# Sensors_A_Data.net
KiCad netlist of a schematic drawn in Altium Designer
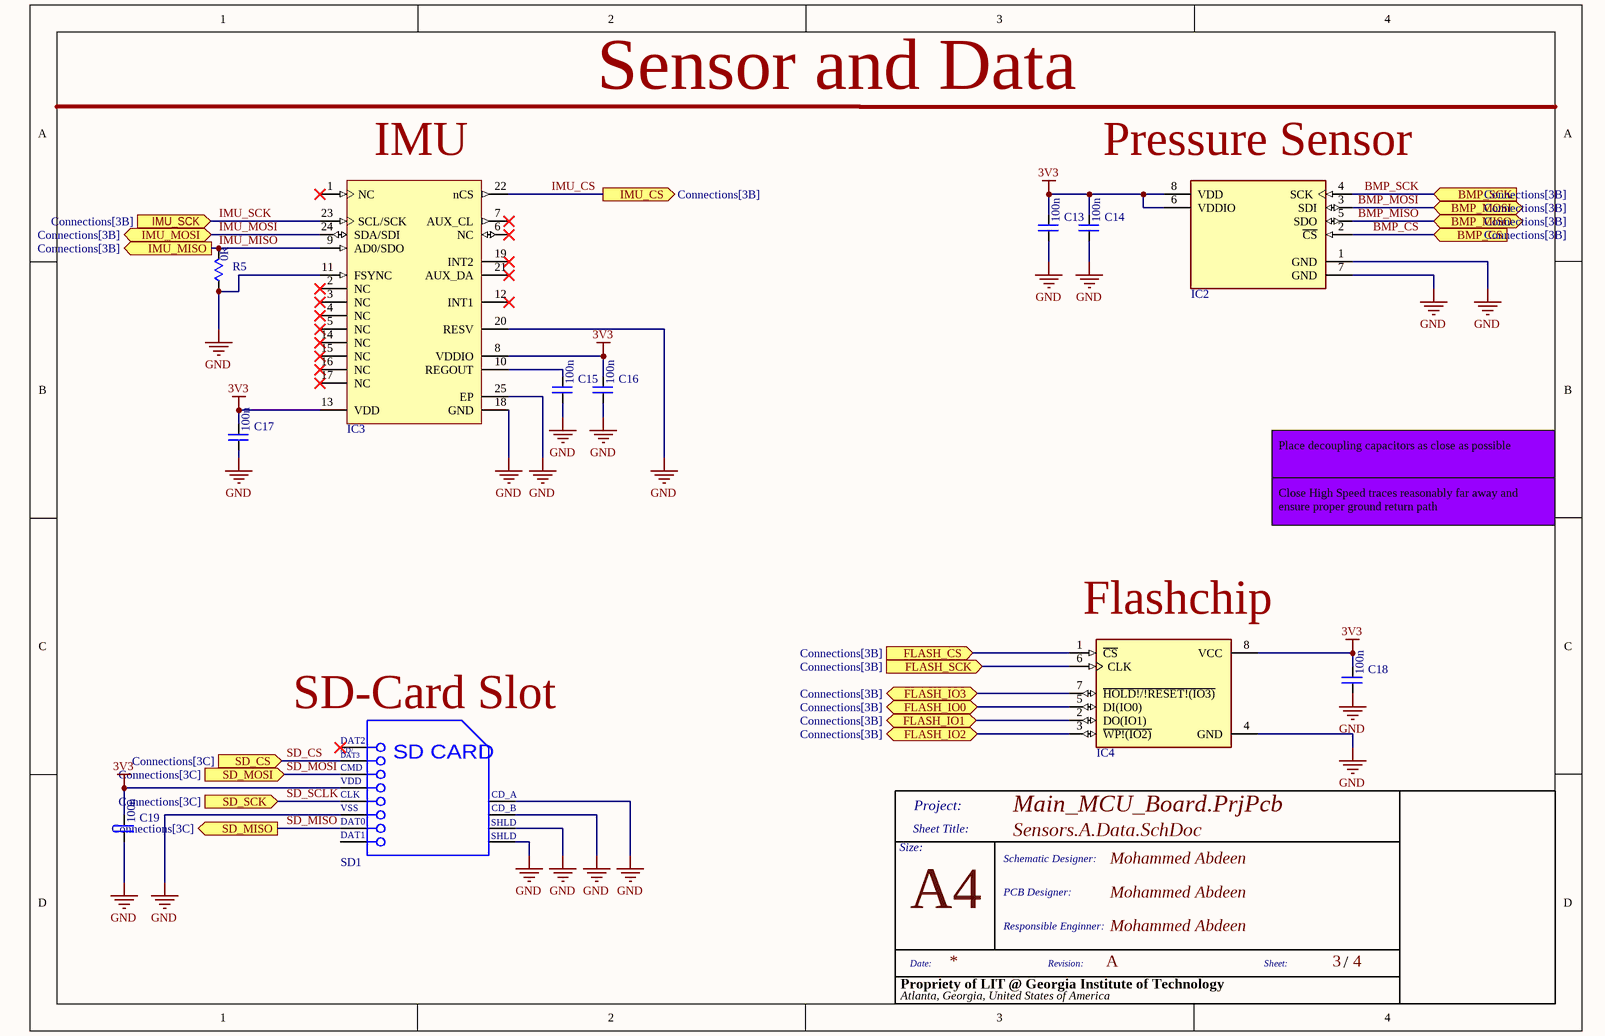
[diagram p0: Sensors.A.Data.SchDoc]

(export (version "E")
  (design (tool "Eeschema 10.0.6"))
  (components
    (comp (ref "C13")
      (value "KGM21NR71E104KT")
      (footprint "CAP-0805")
      (description "0.1 µF ±10% 25V Ceramic Capacitor X7R 0805 (2012 Metric)")
      (libsource (lib "MainMCUSch") (part "CAP-0805-25V-100n"))
    )
    (comp (ref "C14")
      (value "KGM21NR71E104KT")
      (footprint "CAP-0805")
      (description "0.1 µF ±10% 25V Ceramic Capacitor X7R 0805 (2012 Metric)")
      (libsource (lib "MainMCUSch") (part "CAP-0805-25V-100n"))
    )
    (comp (ref "C15")
      (value "KGM21NR71E104KT")
      (footprint "CAP-0805")
      (description "0.1 µF ±10% 25V Ceramic Capacitor X7R 0805 (2012 Metric)")
      (libsource (lib "MainMCUSch") (part "CAP-0805-25V-100n"))
    )
    (comp (ref "C16")
      (value "KGM21NR71E104KT")
      (footprint "CAP-0805")
      (description "0.1 µF ±10% 25V Ceramic Capacitor X7R 0805 (2012 Metric)")
      (libsource (lib "MainMCUSch") (part "CAP-0805-25V-100n"))
    )
    (comp (ref "C17")
      (value "KGM21NR71E104KT")
      (footprint "CAP-0805")
      (description "0.1 µF ±10% 25V Ceramic Capacitor X7R 0805 (2012 Metric)")
      (libsource (lib "MainMCUSch") (part "CAP-0805-25V-100n"))
    )
    (comp (ref "C18")
      (value "KGM21NR71E104KT")
      (footprint "CAP-0805")
      (description "0.1 µF ±10% 25V Ceramic Capacitor X7R 0805 (2012 Metric)")
      (libsource (lib "MainMCUSch") (part "CAP-0805-25V-100n"))
    )
    (comp (ref "C19")
      (value "KGM21NR71E104KT")
      (footprint "CAP-0805")
      (description "0.1 µF ±10% 25V Ceramic Capacitor X7R 0805 (2012 Metric)")
      (libsource (lib "MainMCUSch") (part "CAP-0805-25V-100n"))
    )
    (comp (ref "IC2")
      (value "BME280")
      (footprint "BME280")
      (description "Pressure Sensor 4.35PSI ~ 15.95PSI (30kPa ~ 110kPa) Absolute 16b 8-SMD")
      (libsource (lib "MainMCUSch") (part "BME280"))
    )
    (comp (ref "IC3")
      (value "ICM-20649")
      (footprint "24-QFN")
      (description "Accelerometer, Gyroscope, Temperature, 6 Axis Sensor I2C, SPI Output")
      (libsource (lib "MainMCUSch") (part "IMU-ICM20649-SPI"))
    )
    (comp (ref "IC4")
      (value "W25Q32JVSSIQ")
      (footprint "F-SOIC127P790X216-8N")
      (description "FLASH - NOR Memory IC 32Mbit SPI - Quad I/O 133 MHz 8-SOIC")
      (libsource (lib "MainMCUSch") (part "Flashchip-32MBIT-3V3"))
    )
    (comp (ref "R5")
      (value "ERJ-6GEY0R00V")
      (footprint "0805-RES")
      (description "0 Ohms Jumper Chip Resistor 0805 (2012 Metric) Automotive AEC-Q200 Thick Film")
      (libsource (lib "MainMCUSch") (part "RES-0805-0R"))
    )
    (comp (ref "SD1")
      (value "1040310811")
      (footprint "MOLX-104031-0811_V")
      (description "10 (8 + 2) Position Card Connector Secure Digital - microSD™ Surface Mount, Right Angle Gold")
      (fields (field (name "MANUFACTURER") "Molex"))
      (libsource (lib "MainMCUSch") (part "microSD-card-connector"))
    )
  )
  (nets
    (net (code "1") (name "/BMP_CS") (class "Default")
      (node (ref "IC2") (pin "2") (pinfunction "~{CS}_2") (pintype "input"))
    )
    (net (code "2") (name "/BMP_MISO") (class "Default")
      (node (ref "IC2") (pin "5") (pinfunction "SDO_5") (pintype "bidirectional"))
    )
    (net (code "3") (name "/BMP_MOSI") (class "Default")
      (node (ref "IC2") (pin "3") (pinfunction "SDI_3") (pintype "bidirectional"))
    )
    (net (code "4") (name "/BMP_SCK") (class "Default")
      (node (ref "IC2") (pin "4") (pinfunction "SCK_4") (pintype "input"))
    )
    (net (code "5") (name "/FLASH_CS") (class "Default")
      (node (ref "IC4") (pin "1") (pinfunction "~{CS}_1") (pintype "input"))
    )
    (net (code "6") (name "/FLASH_IO0") (class "Default")
      (node (ref "IC4") (pin "5") (pinfunction "DI(IO0)_5") (pintype "bidirectional"))
    )
    (net (code "7") (name "/FLASH_IO1") (class "Default")
      (node (ref "IC4") (pin "2") (pinfunction "DO(IO1)_2") (pintype "bidirectional"))
    )
    (net (code "8") (name "/FLASH_IO2") (class "Default")
      (node (ref "IC4") (pin "3") (pinfunction "~{WP!(IO2)}_3") (pintype "bidirectional"))
    )
    (net (code "9") (name "/FLASH_IO3") (class "Default")
      (node (ref "IC4") (pin "7") (pinfunction "~{HOLD!/!RESET!(IO3)}_7") (pintype "bidirectional"))
    )
    (net (code "10") (name "/FLASH_SCK") (class "Default")
      (node (ref "IC4") (pin "6") (pinfunction "CLK_6") (pintype "input"))
    )
    (net (code "11") (name "/IMU_CS") (class "Default")
      (node (ref "IC3") (pin "22") (pinfunction "nCS_22") (pintype "output"))
    )
    (net (code "12") (name "/IMU_MISO") (class "Default")
      (node (ref "IC3") (pin "9") (pinfunction "AD0/SDO_9") (pintype "input"))
      (node (ref "R5") (pin "2") (pintype "passive"))
    )
    (net (code "13") (name "/IMU_MOSI") (class "Default")
      (node (ref "IC3") (pin "24") (pinfunction "SDA/SDI_24") (pintype "bidirectional"))
    )
    (net (code "14") (name "/IMU_SCK") (class "Default")
      (node (ref "IC3") (pin "23") (pinfunction "SCL/SCK_23") (pintype "input"))
    )
    (net (code "15") (name "/SD_CS") (class "Default")
      (node (ref "SD1") (pin "2") (pinfunction "CMD_2") (pintype "passive"))
    )
    (net (code "16") (name "/SD_MISO") (class "Default")
      (node (ref "SD1") (pin "7") (pinfunction "DAT0_7") (pintype "passive"))
    )
    (net (code "17") (name "/SD_MOSI") (class "Default")
      (node (ref "SD1") (pin "3") (pinfunction "VSS1_3") (pintype "passive"))
    )
    (net (code "18") (name "/SD_SCLK") (class "Default")
      (node (ref "SD1") (pin "5") (pinfunction "CLK_5") (pintype "passive"))
    )
    (net (code "19") (name "3V3") (class "Default")
      (node (ref "C13") (pin "2") (pintype "passive"))
      (node (ref "C14") (pin "2") (pintype "passive"))
      (node (ref "C16") (pin "2") (pintype "passive"))
      (node (ref "C17") (pin "2") (pintype "passive"))
      (node (ref "C18") (pin "2") (pintype "passive"))
      (node (ref "C19") (pin "2") (pintype "passive"))
      (node (ref "IC2") (pin "6") (pinfunction "VDDIO_6") (pintype "power_in"))
      (node (ref "IC2") (pin "8") (pinfunction "VDD_8") (pintype "power_in"))
      (node (ref "IC3") (pin "13") (pinfunction "VDD_13") (pintype "power_in"))
      (node (ref "IC3") (pin "8") (pinfunction "VDDIO_8") (pintype "power_in"))
      (node (ref "IC4") (pin "8") (pinfunction "VCC_8") (pintype "power_in"))
      (node (ref "SD1") (pin "4") (pinfunction "VDD_4") (pintype "passive"))
    )
    (net (code "20") (name "GND") (class "Default")
      (node (ref "C13") (pin "1") (pintype "passive"))
      (node (ref "C14") (pin "1") (pintype "passive"))
      (node (ref "C15") (pin "1") (pintype "passive"))
      (node (ref "C16") (pin "1") (pintype "passive"))
      (node (ref "C17") (pin "1") (pintype "passive"))
      (node (ref "C18") (pin "1") (pintype "passive"))
      (node (ref "C19") (pin "1") (pintype "passive"))
      (node (ref "IC2") (pin "1") (pinfunction "GND_1") (pintype "power_in"))
      (node (ref "IC2") (pin "7") (pinfunction "GND_7") (pintype "power_in"))
      (node (ref "IC3") (pin "11") (pinfunction "FSYNC_11") (pintype "input"))
      (node (ref "IC3") (pin "18") (pinfunction "GND_18") (pintype "power_in"))
      (node (ref "IC3") (pin "20") (pinfunction "RESV_20") (pintype "passive"))
      (node (ref "IC3") (pin "25") (pinfunction "EP_25") (pintype "power_in"))
      (node (ref "IC4") (pin "4") (pinfunction "GND_4") (pintype "power_in"))
      (node (ref "R5") (pin "1") (pintype "passive"))
      (node (ref "SD1") (pin "10") (pinfunction "CD_B_10") (pintype "passive"))
      (node (ref "SD1") (pin "11") (pinfunction "SHLD1_11") (pintype "passive"))
      (node (ref "SD1") (pin "12") (pinfunction "SHLD2_12") (pintype "passive"))
      (node (ref "SD1") (pin "6") (pinfunction "VSS2_6") (pintype "passive"))
      (node (ref "SD1") (pin "9") (pinfunction "CD_A_9") (pintype "passive"))
    )
    (net (code "21") (name "Net-(IC3-REGOUT)") (class "Default")
      (node (ref "C15") (pin "2") (pintype "passive"))
      (node (ref "IC3") (pin "10") (pinfunction "REGOUT_10") (pintype "passive"))
    )
    (net (code "22") (name "unconnected-(IC3-AUX_CL-Pad7)") (class "Default")
      (node (ref "IC3") (pin "7") (pinfunction "AUX_CL_7") (pintype "output+no_connect"))
    )
    (net (code "23") (name "unconnected-(IC3-AUX_DA-Pad21)") (class "Default")
      (node (ref "IC3") (pin "21") (pinfunction "AUX_DA_21") (pintype "passive+no_connect"))
    )
    (net (code "24") (name "unconnected-(IC3-INT1-Pad12)") (class "Default")
      (node (ref "IC3") (pin "12") (pinfunction "INT1_12") (pintype "open_collector+no_connect"))
    )
    (net (code "25") (name "unconnected-(IC3-INT2-Pad19)") (class "Default")
      (node (ref "IC3") (pin "19") (pinfunction "INT2_19") (pintype "passive+no_connect"))
    )
    (net (code "26") (name "unconnected-(IC3-NC-Pad1)") (class "Default")
      (node (ref "IC3") (pin "1") (pinfunction "NC_1") (pintype "input+no_connect"))
    )
    (net (code "27") (name "unconnected-(IC3-NC-Pad2)") (class "Default")
      (node (ref "IC3") (pin "2") (pinfunction "NC_2") (pintype "passive+no_connect"))
    )
    (net (code "28") (name "unconnected-(IC3-NC-Pad3)") (class "Default")
      (node (ref "IC3") (pin "3") (pinfunction "NC_3") (pintype "passive+no_connect"))
    )
    (net (code "29") (name "unconnected-(IC3-NC-Pad4)") (class "Default")
      (node (ref "IC3") (pin "4") (pinfunction "NC_4") (pintype "passive+no_connect"))
    )
    (net (code "30") (name "unconnected-(IC3-NC-Pad5)") (class "Default")
      (node (ref "IC3") (pin "5") (pinfunction "NC_5") (pintype "passive+no_connect"))
    )
    (net (code "31") (name "unconnected-(IC3-NC-Pad6)") (class "Default")
      (node (ref "IC3") (pin "6") (pinfunction "NC_6") (pintype "bidirectional+no_connect"))
    )
    (net (code "32") (name "unconnected-(IC3-NC-Pad14)") (class "Default")
      (node (ref "IC3") (pin "14") (pinfunction "NC_14") (pintype "passive+no_connect"))
    )
    (net (code "33") (name "unconnected-(IC3-NC-Pad15)") (class "Default")
      (node (ref "IC3") (pin "15") (pinfunction "NC_15") (pintype "passive+no_connect"))
    )
    (net (code "34") (name "unconnected-(IC3-NC-Pad16)") (class "Default")
      (node (ref "IC3") (pin "16") (pinfunction "NC_16") (pintype "passive+no_connect"))
    )
    (net (code "35") (name "unconnected-(IC3-NC-Pad17)") (class "Default")
      (node (ref "IC3") (pin "17") (pinfunction "NC_17") (pintype "passive+no_connect"))
    )
    (net (code "36") (name "unconnected-(SD1-CD{slash}DAT3-Pad1)") (class "Default")
      (node (ref "SD1") (pin "1") (pinfunction "CD/DAT3_1") (pintype "passive+no_connect"))
    )
    (net (code "37") (name "unconnected-(SD1-DAT1-Pad8)") (class "Default")
      (node (ref "SD1") (pin "8") (pinfunction "DAT1_8") (pintype "passive"))
    )
  )
)
